# clock.net
KiCad netlist of a schematic drawn in EAGLE
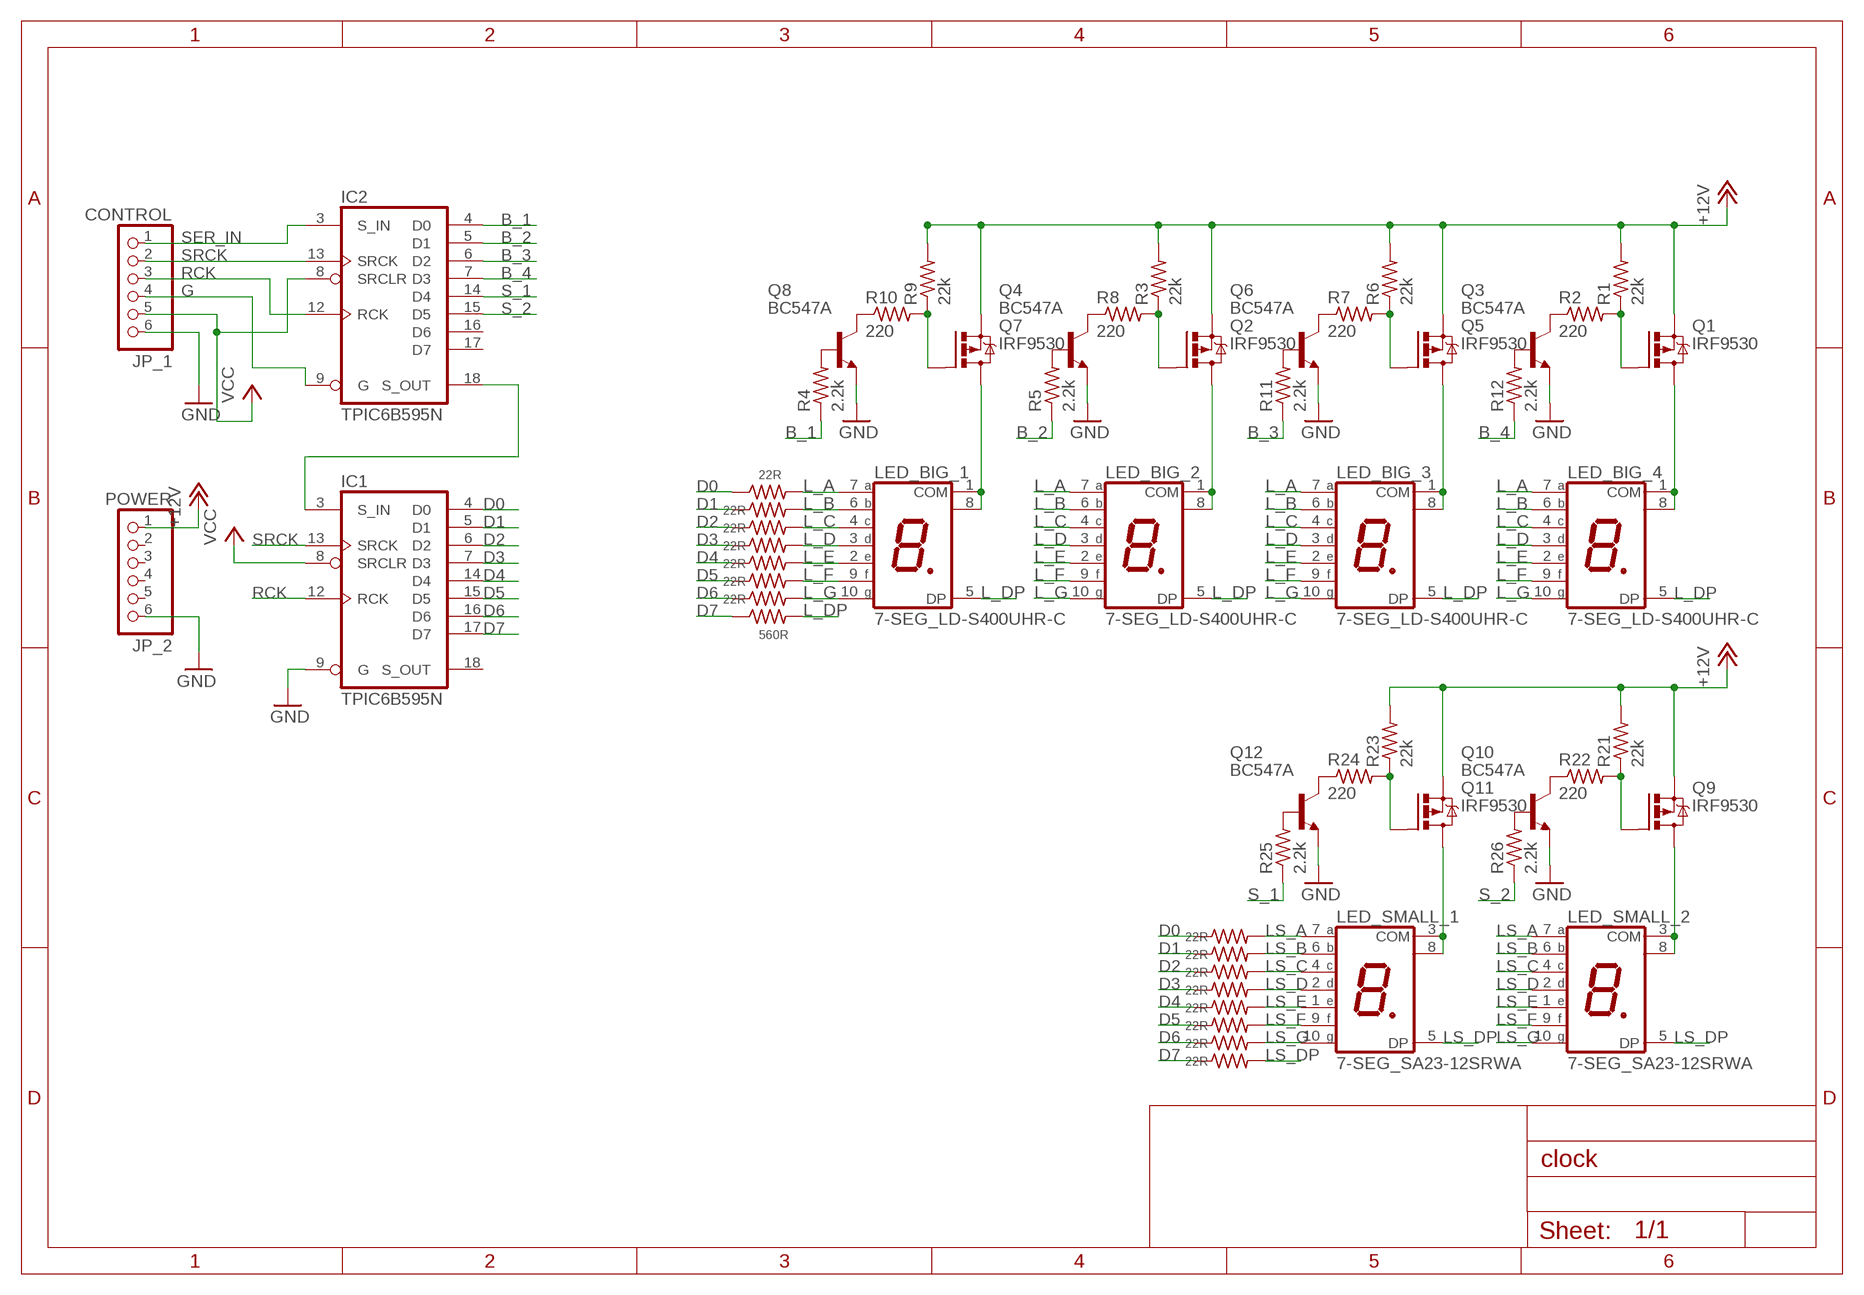
[diagram p0: schematic, sheet 1]

(export (version "E")
  (design (tool "Eeschema 10.0.6"))
  (components
    (comp (ref "CONTROL")
      (value "JP_1")
      (footprint "eagle-import:1X06")
      (libsource (lib "eagle-import") (part "PINHD-1X6"))
    )
    (comp (ref "IC1")
      (value "TPIC6B595N")
      (footprint "eagle-import:DIL20")
      (libsource (lib "eagle-import") (part "TPIC6B595N"))
    )
    (comp (ref "IC2")
      (value "TPIC6B595N")
      (footprint "eagle-import:DIL20")
      (libsource (lib "eagle-import") (part "TPIC6B595N"))
    )
    (comp (ref "LED_BIG_1")
      (value "7-SEG_LD-S400UHR-C")
      (footprint "eagle-import:LD-S400UHR-C")
      (libsource (lib "eagle-import") (part "7-SEG_LD-S400UHR-C"))
    )
    (comp (ref "LED_BIG_2")
      (value "7-SEG_LD-S400UHR-C")
      (footprint "eagle-import:LD-S400UHR-C")
      (libsource (lib "eagle-import") (part "7-SEG_LD-S400UHR-C"))
    )
    (comp (ref "LED_BIG_3")
      (value "7-SEG_LD-S400UHR-C")
      (footprint "eagle-import:LD-S400UHR-C")
      (libsource (lib "eagle-import") (part "7-SEG_LD-S400UHR-C"))
    )
    (comp (ref "LED_BIG_4")
      (value "7-SEG_LD-S400UHR-C")
      (footprint "eagle-import:LD-S400UHR-C")
      (libsource (lib "eagle-import") (part "7-SEG_LD-S400UHR-C"))
    )
    (comp (ref "LED_SMALL_1")
      (value "7-SEG_SA23-12SRWA")
      (footprint "eagle-import:SA23-12SRWA")
      (libsource (lib "eagle-import") (part "7-SEG_SA23-12SRWA"))
    )
    (comp (ref "LED_SMALL_2")
      (value "7-SEG_SA23-12SRWA")
      (footprint "eagle-import:SA23-12SRWA")
      (libsource (lib "eagle-import") (part "7-SEG_SA23-12SRWA"))
    )
    (comp (ref "POWER")
      (value "JP_2")
      (footprint "eagle-import:1X06")
      (libsource (lib "eagle-import") (part "PINHD-1X6"))
    )
    (comp (ref "Q1")
      (value "IRF9530")
      (footprint "eagle-import:TO220BV")
      (libsource (lib "eagle-import") (part "IRF9530"))
    )
    (comp (ref "Q2")
      (value "IRF9530")
      (footprint "eagle-import:TO220BV")
      (libsource (lib "eagle-import") (part "IRF9530"))
    )
    (comp (ref "Q3")
      (value "BC547A")
      (footprint "eagle-import:TO92")
      (libsource (lib "eagle-import") (part "BC547A"))
    )
    (comp (ref "Q4")
      (value "BC547A")
      (footprint "eagle-import:TO92")
      (libsource (lib "eagle-import") (part "BC547A"))
    )
    (comp (ref "Q5")
      (value "IRF9530")
      (footprint "eagle-import:TO220BV")
      (libsource (lib "eagle-import") (part "IRF9530"))
    )
    (comp (ref "Q6")
      (value "BC547A")
      (footprint "eagle-import:TO92")
      (libsource (lib "eagle-import") (part "BC547A"))
    )
    (comp (ref "Q7")
      (value "IRF9530")
      (footprint "eagle-import:TO220BV")
      (libsource (lib "eagle-import") (part "IRF9530"))
    )
    (comp (ref "Q8")
      (value "BC547A")
      (footprint "eagle-import:TO92")
      (libsource (lib "eagle-import") (part "BC547A"))
    )
    (comp (ref "Q9")
      (value "IRF9530")
      (footprint "eagle-import:TO220BV")
      (libsource (lib "eagle-import") (part "IRF9530"))
    )
    (comp (ref "Q10")
      (value "BC547A")
      (footprint "eagle-import:TO92")
      (libsource (lib "eagle-import") (part "BC547A"))
    )
    (comp (ref "Q11")
      (value "IRF9530")
      (footprint "eagle-import:TO220BV")
      (libsource (lib "eagle-import") (part "IRF9530"))
    )
    (comp (ref "Q12")
      (value "BC547A")
      (footprint "eagle-import:TO92")
      (libsource (lib "eagle-import") (part "BC547A"))
    )
    (comp (ref "R1")
      (value "22k")
      (footprint "eagle-import:0207_12")
      (libsource (lib "eagle-import") (part "R-US_0207/12"))
    )
    (comp (ref "R2")
      (value "220")
      (footprint "eagle-import:0207_12")
      (libsource (lib "eagle-import") (part "R-US_0207/12"))
    )
    (comp (ref "R3")
      (value "22k")
      (footprint "eagle-import:0207_12")
      (libsource (lib "eagle-import") (part "R-US_0207/12"))
    )
    (comp (ref "R4")
      (value "2.2k")
      (footprint "eagle-import:0207_12")
      (libsource (lib "eagle-import") (part "R-US_0207/12"))
    )
    (comp (ref "R5")
      (value "2.2k")
      (footprint "eagle-import:0207_12")
      (libsource (lib "eagle-import") (part "R-US_0207/12"))
    )
    (comp (ref "R6")
      (value "22k")
      (footprint "eagle-import:0207_12")
      (libsource (lib "eagle-import") (part "R-US_0207/12"))
    )
    (comp (ref "R7")
      (value "220")
      (footprint "eagle-import:0207_12")
      (libsource (lib "eagle-import") (part "R-US_0207/12"))
    )
    (comp (ref "R8")
      (value "220")
      (footprint "eagle-import:0207_12")
      (libsource (lib "eagle-import") (part "R-US_0207/12"))
    )
    (comp (ref "R9")
      (value "22k")
      (footprint "eagle-import:0207_12")
      (libsource (lib "eagle-import") (part "R-US_0207/12"))
    )
    (comp (ref "R10")
      (value "220")
      (footprint "eagle-import:0207_12")
      (libsource (lib "eagle-import") (part "R-US_0207/12"))
    )
    (comp (ref "R11")
      (value "2.2k")
      (footprint "eagle-import:0207_12")
      (libsource (lib "eagle-import") (part "R-US_0207/12"))
    )
    (comp (ref "R12")
      (value "2.2k")
      (footprint "eagle-import:0207_12")
      (libsource (lib "eagle-import") (part "R-US_0207/12"))
    )
    (comp (ref "R13")
      (value "22R")
      (footprint "eagle-import:0207_12")
      (libsource (lib "eagle-import") (part "R-US_0207/12"))
    )
    (comp (ref "R14")
      (value "22R")
      (footprint "eagle-import:0207_12")
      (libsource (lib "eagle-import") (part "R-US_0207/12"))
    )
    (comp (ref "R15")
      (value "22R")
      (footprint "eagle-import:0207_12")
      (libsource (lib "eagle-import") (part "R-US_0207/12"))
    )
    (comp (ref "R16")
      (value "22R")
      (footprint "eagle-import:0207_12")
      (libsource (lib "eagle-import") (part "R-US_0207/12"))
    )
    (comp (ref "R17")
      (value "22R")
      (footprint "eagle-import:0207_12")
      (libsource (lib "eagle-import") (part "R-US_0207/12"))
    )
    (comp (ref "R18")
      (value "22R")
      (footprint "eagle-import:0207_12")
      (libsource (lib "eagle-import") (part "R-US_0207/12"))
    )
    (comp (ref "R19")
      (value "22R")
      (footprint "eagle-import:0207_12")
      (libsource (lib "eagle-import") (part "R-US_0207/12"))
    )
    (comp (ref "R20")
      (value "560R")
      (footprint "eagle-import:0207_12")
      (libsource (lib "eagle-import") (part "R-US_0207/12"))
    )
    (comp (ref "R21")
      (value "22k")
      (footprint "eagle-import:0207_12")
      (libsource (lib "eagle-import") (part "R-US_0207/12"))
    )
    (comp (ref "R22")
      (value "220")
      (footprint "eagle-import:0207_12")
      (libsource (lib "eagle-import") (part "R-US_0207/12"))
    )
    (comp (ref "R23")
      (value "22k")
      (footprint "eagle-import:0207_12")
      (libsource (lib "eagle-import") (part "R-US_0207/12"))
    )
    (comp (ref "R24")
      (value "220")
      (footprint "eagle-import:0207_12")
      (libsource (lib "eagle-import") (part "R-US_0207/12"))
    )
    (comp (ref "R25")
      (value "2.2k")
      (footprint "eagle-import:0207_12")
      (libsource (lib "eagle-import") (part "R-US_0207/12"))
    )
    (comp (ref "R26")
      (value "2.2k")
      (footprint "eagle-import:0207_12")
      (libsource (lib "eagle-import") (part "R-US_0207/12"))
    )
    (comp (ref "R27")
      (value "22R")
      (footprint "eagle-import:0207_12")
      (libsource (lib "eagle-import") (part "R-US_0207/12"))
    )
    (comp (ref "R28")
      (value "22R")
      (footprint "eagle-import:0207_12")
      (libsource (lib "eagle-import") (part "R-US_0207/12"))
    )
    (comp (ref "R29")
      (value "22R")
      (footprint "eagle-import:0207_12")
      (libsource (lib "eagle-import") (part "R-US_0207/12"))
    )
    (comp (ref "R30")
      (value "22R")
      (footprint "eagle-import:0207_12")
      (libsource (lib "eagle-import") (part "R-US_0207/12"))
    )
    (comp (ref "R31")
      (value "22R")
      (footprint "eagle-import:0207_12")
      (libsource (lib "eagle-import") (part "R-US_0207/12"))
    )
    (comp (ref "R32")
      (value "22R")
      (footprint "eagle-import:0207_12")
      (libsource (lib "eagle-import") (part "R-US_0207/12"))
    )
    (comp (ref "R33")
      (value "22R")
      (footprint "eagle-import:0207_12")
      (libsource (lib "eagle-import") (part "R-US_0207/12"))
    )
    (comp (ref "R34")
      (value "22R")
      (footprint "eagle-import:0207_12")
      (libsource (lib "eagle-import") (part "R-US_0207/12"))
    )
  )
  (nets
    (net (code "1") (name "+12V") (class "Default")
      (node (ref "POWER") (pin "1") (pinfunction "1_1") (pintype "passive"))
      (node (ref "Q1") (pin "S") (pinfunction "S_S") (pintype "passive"))
      (node (ref "Q11") (pin "S") (pinfunction "S_S") (pintype "passive"))
      (node (ref "Q2") (pin "S") (pinfunction "S_S") (pintype "passive"))
      (node (ref "Q5") (pin "S") (pinfunction "S_S") (pintype "passive"))
      (node (ref "Q7") (pin "S") (pinfunction "S_S") (pintype "passive"))
      (node (ref "Q9") (pin "S") (pinfunction "S_S") (pintype "passive"))
      (node (ref "R1") (pin "2") (pinfunction "2_2") (pintype "passive"))
      (node (ref "R21") (pin "2") (pinfunction "2_2") (pintype "passive"))
      (node (ref "R23") (pin "2") (pinfunction "2_2") (pintype "passive"))
      (node (ref "R3") (pin "2") (pinfunction "2_2") (pintype "passive"))
      (node (ref "R6") (pin "2") (pinfunction "2_2") (pintype "passive"))
      (node (ref "R9") (pin "2") (pinfunction "2_2") (pintype "passive"))
    )
    (net (code "2") (name "/B_1") (class "Default")
      (node (ref "IC2") (pin "4") (pinfunction "D0_4") (pintype "tri_state"))
      (node (ref "R4") (pin "1") (pinfunction "1_1") (pintype "passive"))
    )
    (net (code "3") (name "/B_2") (class "Default")
      (node (ref "IC2") (pin "5") (pinfunction "D1_5") (pintype "tri_state"))
      (node (ref "R5") (pin "1") (pinfunction "1_1") (pintype "passive"))
    )
    (net (code "4") (name "/B_3") (class "Default")
      (node (ref "IC2") (pin "6") (pinfunction "D2_6") (pintype "tri_state"))
      (node (ref "R11") (pin "1") (pinfunction "1_1") (pintype "passive"))
    )
    (net (code "5") (name "/B_4") (class "Default")
      (node (ref "IC2") (pin "7") (pinfunction "D3_7") (pintype "tri_state"))
      (node (ref "R12") (pin "1") (pinfunction "1_1") (pintype "passive"))
    )
    (net (code "6") (name "/D0") (class "Default")
      (node (ref "IC1") (pin "4") (pinfunction "D0_4") (pintype "tri_state"))
      (node (ref "R13") (pin "1") (pinfunction "1_1") (pintype "passive"))
      (node (ref "R27") (pin "1") (pinfunction "1_1") (pintype "passive"))
    )
    (net (code "7") (name "/D1") (class "Default")
      (node (ref "IC1") (pin "5") (pinfunction "D1_5") (pintype "tri_state"))
      (node (ref "R14") (pin "1") (pinfunction "1_1") (pintype "passive"))
      (node (ref "R28") (pin "1") (pinfunction "1_1") (pintype "passive"))
    )
    (net (code "8") (name "/D2") (class "Default")
      (node (ref "IC1") (pin "6") (pinfunction "D2_6") (pintype "tri_state"))
      (node (ref "R15") (pin "1") (pinfunction "1_1") (pintype "passive"))
      (node (ref "R29") (pin "1") (pinfunction "1_1") (pintype "passive"))
    )
    (net (code "9") (name "/D3") (class "Default")
      (node (ref "IC1") (pin "7") (pinfunction "D3_7") (pintype "tri_state"))
      (node (ref "R16") (pin "1") (pinfunction "1_1") (pintype "passive"))
      (node (ref "R30") (pin "1") (pinfunction "1_1") (pintype "passive"))
    )
    (net (code "10") (name "/D4") (class "Default")
      (node (ref "IC1") (pin "14") (pinfunction "D4_14") (pintype "tri_state"))
      (node (ref "R17") (pin "1") (pinfunction "1_1") (pintype "passive"))
      (node (ref "R31") (pin "1") (pinfunction "1_1") (pintype "passive"))
    )
    (net (code "11") (name "/D5") (class "Default")
      (node (ref "IC1") (pin "15") (pinfunction "D5_15") (pintype "tri_state"))
      (node (ref "R18") (pin "1") (pinfunction "1_1") (pintype "passive"))
      (node (ref "R32") (pin "1") (pinfunction "1_1") (pintype "passive"))
    )
    (net (code "12") (name "/D6") (class "Default")
      (node (ref "IC1") (pin "16") (pinfunction "D6_16") (pintype "tri_state"))
      (node (ref "R19") (pin "1") (pinfunction "1_1") (pintype "passive"))
      (node (ref "R33") (pin "1") (pinfunction "1_1") (pintype "passive"))
    )
    (net (code "13") (name "/D7") (class "Default")
      (node (ref "IC1") (pin "17") (pinfunction "D7_17") (pintype "tri_state"))
      (node (ref "R20") (pin "1") (pinfunction "1_1") (pintype "passive"))
      (node (ref "R34") (pin "1") (pinfunction "1_1") (pintype "passive"))
    )
    (net (code "14") (name "/G") (class "Default")
      (node (ref "CONTROL") (pin "4") (pinfunction "4_4") (pintype "passive"))
      (node (ref "IC2") (pin "9") (pinfunction "G_9") (pintype "input"))
    )
    (net (code "15") (name "/LS_A") (class "Default")
      (node (ref "LED_SMALL_1") (pin "7") (pinfunction "A_7") (pintype "passive"))
      (node (ref "LED_SMALL_2") (pin "7") (pinfunction "A_7") (pintype "passive"))
      (node (ref "R27") (pin "2") (pinfunction "2_2") (pintype "passive"))
    )
    (net (code "16") (name "/LS_B") (class "Default")
      (node (ref "LED_SMALL_1") (pin "6") (pinfunction "B_6") (pintype "passive"))
      (node (ref "LED_SMALL_2") (pin "6") (pinfunction "B_6") (pintype "passive"))
      (node (ref "R28") (pin "2") (pinfunction "2_2") (pintype "passive"))
    )
    (net (code "17") (name "/LS_C") (class "Default")
      (node (ref "LED_SMALL_1") (pin "4") (pinfunction "C_4") (pintype "passive"))
      (node (ref "LED_SMALL_2") (pin "4") (pinfunction "C_4") (pintype "passive"))
      (node (ref "R29") (pin "2") (pinfunction "2_2") (pintype "passive"))
    )
    (net (code "18") (name "/LS_D") (class "Default")
      (node (ref "LED_SMALL_1") (pin "2") (pinfunction "D_2") (pintype "passive"))
      (node (ref "LED_SMALL_2") (pin "2") (pinfunction "D_2") (pintype "passive"))
      (node (ref "R30") (pin "2") (pinfunction "2_2") (pintype "passive"))
    )
    (net (code "19") (name "/LS_DP") (class "Default")
      (node (ref "LED_SMALL_1") (pin "5") (pinfunction "DP_5") (pintype "passive"))
      (node (ref "LED_SMALL_2") (pin "5") (pinfunction "DP_5") (pintype "passive"))
      (node (ref "R34") (pin "2") (pinfunction "2_2") (pintype "passive"))
    )
    (net (code "20") (name "/LS_E") (class "Default")
      (node (ref "LED_SMALL_1") (pin "1") (pinfunction "E_1") (pintype "passive"))
      (node (ref "LED_SMALL_2") (pin "1") (pinfunction "E_1") (pintype "passive"))
      (node (ref "R31") (pin "2") (pinfunction "2_2") (pintype "passive"))
    )
    (net (code "21") (name "/LS_F") (class "Default")
      (node (ref "LED_SMALL_1") (pin "9") (pinfunction "F_9") (pintype "passive"))
      (node (ref "LED_SMALL_2") (pin "9") (pinfunction "F_9") (pintype "passive"))
      (node (ref "R32") (pin "2") (pinfunction "2_2") (pintype "passive"))
    )
    (net (code "22") (name "/LS_G") (class "Default")
      (node (ref "LED_SMALL_1") (pin "10") (pinfunction "G_10") (pintype "passive"))
      (node (ref "LED_SMALL_2") (pin "10") (pinfunction "G_10") (pintype "passive"))
      (node (ref "R33") (pin "2") (pinfunction "2_2") (pintype "passive"))
    )
    (net (code "23") (name "/L_A") (class "Default")
      (node (ref "LED_BIG_1") (pin "7") (pinfunction "A_7") (pintype "passive"))
      (node (ref "LED_BIG_2") (pin "7") (pinfunction "A_7") (pintype "passive"))
      (node (ref "LED_BIG_3") (pin "7") (pinfunction "A_7") (pintype "passive"))
      (node (ref "LED_BIG_4") (pin "7") (pinfunction "A_7") (pintype "passive"))
      (node (ref "R13") (pin "2") (pinfunction "2_2") (pintype "passive"))
    )
    (net (code "24") (name "/L_B") (class "Default")
      (node (ref "LED_BIG_1") (pin "6") (pinfunction "B_6") (pintype "passive"))
      (node (ref "LED_BIG_2") (pin "6") (pinfunction "B_6") (pintype "passive"))
      (node (ref "LED_BIG_3") (pin "6") (pinfunction "B_6") (pintype "passive"))
      (node (ref "LED_BIG_4") (pin "6") (pinfunction "B_6") (pintype "passive"))
      (node (ref "R14") (pin "2") (pinfunction "2_2") (pintype "passive"))
    )
    (net (code "25") (name "/L_C") (class "Default")
      (node (ref "LED_BIG_1") (pin "4") (pinfunction "C_4") (pintype "passive"))
      (node (ref "LED_BIG_2") (pin "4") (pinfunction "C_4") (pintype "passive"))
      (node (ref "LED_BIG_3") (pin "4") (pinfunction "C_4") (pintype "passive"))
      (node (ref "LED_BIG_4") (pin "4") (pinfunction "C_4") (pintype "passive"))
      (node (ref "R15") (pin "2") (pinfunction "2_2") (pintype "passive"))
    )
    (net (code "26") (name "/L_D") (class "Default")
      (node (ref "LED_BIG_1") (pin "3") (pinfunction "D_3") (pintype "passive"))
      (node (ref "LED_BIG_2") (pin "3") (pinfunction "D_3") (pintype "passive"))
      (node (ref "LED_BIG_3") (pin "3") (pinfunction "D_3") (pintype "passive"))
      (node (ref "LED_BIG_4") (pin "3") (pinfunction "D_3") (pintype "passive"))
      (node (ref "R16") (pin "2") (pinfunction "2_2") (pintype "passive"))
    )
    (net (code "27") (name "/L_DP") (class "Default")
      (node (ref "LED_BIG_1") (pin "5") (pinfunction "DP_5") (pintype "passive"))
      (node (ref "LED_BIG_2") (pin "5") (pinfunction "DP_5") (pintype "passive"))
      (node (ref "LED_BIG_3") (pin "5") (pinfunction "DP_5") (pintype "passive"))
      (node (ref "LED_BIG_4") (pin "5") (pinfunction "DP_5") (pintype "passive"))
      (node (ref "R20") (pin "2") (pinfunction "2_2") (pintype "passive"))
    )
    (net (code "28") (name "/L_E") (class "Default")
      (node (ref "LED_BIG_1") (pin "2") (pinfunction "E_2") (pintype "passive"))
      (node (ref "LED_BIG_2") (pin "2") (pinfunction "E_2") (pintype "passive"))
      (node (ref "LED_BIG_3") (pin "2") (pinfunction "E_2") (pintype "passive"))
      (node (ref "LED_BIG_4") (pin "2") (pinfunction "E_2") (pintype "passive"))
      (node (ref "R17") (pin "2") (pinfunction "2_2") (pintype "passive"))
    )
    (net (code "29") (name "/L_F") (class "Default")
      (node (ref "LED_BIG_1") (pin "9") (pinfunction "F_9") (pintype "passive"))
      (node (ref "LED_BIG_2") (pin "9") (pinfunction "F_9") (pintype "passive"))
      (node (ref "LED_BIG_3") (pin "9") (pinfunction "F_9") (pintype "passive"))
      (node (ref "LED_BIG_4") (pin "9") (pinfunction "F_9") (pintype "passive"))
      (node (ref "R18") (pin "2") (pinfunction "2_2") (pintype "passive"))
    )
    (net (code "30") (name "/L_G") (class "Default")
      (node (ref "LED_BIG_1") (pin "10") (pinfunction "G_10") (pintype "passive"))
      (node (ref "LED_BIG_2") (pin "10") (pinfunction "G_10") (pintype "passive"))
      (node (ref "LED_BIG_3") (pin "10") (pinfunction "G_10") (pintype "passive"))
      (node (ref "LED_BIG_4") (pin "10") (pinfunction "G_10") (pintype "passive"))
      (node (ref "R19") (pin "2") (pinfunction "2_2") (pintype "passive"))
    )
    (net (code "31") (name "/RCK") (class "Default")
      (node (ref "CONTROL") (pin "3") (pinfunction "3_3") (pintype "passive"))
      (node (ref "IC1") (pin "12") (pinfunction "RCK_12") (pintype "input"))
      (node (ref "IC2") (pin "12") (pinfunction "RCK_12") (pintype "input"))
    )
    (net (code "32") (name "/SER_IN") (class "Default")
      (node (ref "CONTROL") (pin "1") (pinfunction "1_1") (pintype "passive"))
      (node (ref "IC2") (pin "3") (pinfunction "S_IN_3") (pintype "input"))
    )
    (net (code "33") (name "/SRCK") (class "Default")
      (node (ref "CONTROL") (pin "2") (pinfunction "2_2") (pintype "passive"))
      (node (ref "IC1") (pin "13") (pinfunction "SRCK_13") (pintype "input"))
      (node (ref "IC2") (pin "13") (pinfunction "SRCK_13") (pintype "input"))
    )
    (net (code "34") (name "/S_1") (class "Default")
      (node (ref "IC2") (pin "14") (pinfunction "D4_14") (pintype "tri_state"))
      (node (ref "R25") (pin "1") (pinfunction "1_1") (pintype "passive"))
    )
    (net (code "35") (name "/S_2") (class "Default")
      (node (ref "IC2") (pin "15") (pinfunction "D5_15") (pintype "tri_state"))
      (node (ref "R26") (pin "1") (pinfunction "1_1") (pintype "passive"))
    )
    (net (code "36") (name "GND") (class "Default")
      (node (ref "CONTROL") (pin "6") (pinfunction "6_6") (pintype "passive"))
      (node (ref "IC1") (pin "9") (pinfunction "G_9") (pintype "input"))
      (node (ref "POWER") (pin "6") (pinfunction "6_6") (pintype "passive"))
      (node (ref "Q10") (pin "1") (pinfunction "E_1") (pintype "passive"))
      (node (ref "Q12") (pin "1") (pinfunction "E_1") (pintype "passive"))
      (node (ref "Q3") (pin "1") (pinfunction "E_1") (pintype "passive"))
      (node (ref "Q4") (pin "1") (pinfunction "E_1") (pintype "passive"))
      (node (ref "Q6") (pin "1") (pinfunction "E_1") (pintype "passive"))
      (node (ref "Q8") (pin "1") (pinfunction "E_1") (pintype "passive"))
    )
    (net (code "37") (name "Net-(IC1A-S_IN)") (class "Default")
      (node (ref "IC1") (pin "3") (pinfunction "S_IN_3") (pintype "input"))
      (node (ref "IC2") (pin "18") (pinfunction "S_OUT_18") (pintype "tri_state"))
    )
    (net (code "38") (name "Net-(LED_BIG_1-COM-Pad1)") (class "Default")
      (node (ref "LED_BIG_1") (pin "1") (pinfunction "COM_1") (pintype "passive"))
      (node (ref "LED_BIG_1") (pin "8") (pinfunction "COM_8") (pintype "passive"))
      (node (ref "Q7") (pin "D") (pinfunction "D_D") (pintype "passive"))
    )
    (net (code "39") (name "Net-(LED_BIG_2-COM-Pad1)") (class "Default")
      (node (ref "LED_BIG_2") (pin "1") (pinfunction "COM_1") (pintype "passive"))
      (node (ref "LED_BIG_2") (pin "8") (pinfunction "COM_8") (pintype "passive"))
      (node (ref "Q2") (pin "D") (pinfunction "D_D") (pintype "passive"))
    )
    (net (code "40") (name "Net-(LED_BIG_3-COM-Pad1)") (class "Default")
      (node (ref "LED_BIG_3") (pin "1") (pinfunction "COM_1") (pintype "passive"))
      (node (ref "LED_BIG_3") (pin "8") (pinfunction "COM_8") (pintype "passive"))
      (node (ref "Q5") (pin "D") (pinfunction "D_D") (pintype "passive"))
    )
    (net (code "41") (name "Net-(LED_BIG_4-COM-Pad1)") (class "Default")
      (node (ref "LED_BIG_4") (pin "1") (pinfunction "COM_1") (pintype "passive"))
      (node (ref "LED_BIG_4") (pin "8") (pinfunction "COM_8") (pintype "passive"))
      (node (ref "Q1") (pin "D") (pinfunction "D_D") (pintype "passive"))
    )
    (net (code "42") (name "Net-(LED_SMALL_1-COM-Pad3)") (class "Default")
      (node (ref "LED_SMALL_1") (pin "3") (pinfunction "COM_3") (pintype "passive"))
      (node (ref "LED_SMALL_1") (pin "8") (pinfunction "COM_8") (pintype "passive"))
      (node (ref "Q11") (pin "D") (pinfunction "D_D") (pintype "passive"))
    )
    (net (code "43") (name "Net-(LED_SMALL_2-COM-Pad3)") (class "Default")
      (node (ref "LED_SMALL_2") (pin "3") (pinfunction "COM_3") (pintype "passive"))
      (node (ref "LED_SMALL_2") (pin "8") (pinfunction "COM_8") (pintype "passive"))
      (node (ref "Q9") (pin "D") (pinfunction "D_D") (pintype "passive"))
    )
    (net (code "44") (name "Net-(Q1-PadG)") (class "Default")
      (node (ref "Q1") (pin "G") (pinfunction "G_G") (pintype "passive"))
      (node (ref "R1") (pin "1") (pinfunction "1_1") (pintype "passive"))
      (node (ref "R2") (pin "2") (pinfunction "2_2") (pintype "passive"))
    )
    (net (code "45") (name "Net-(Q2-PadG)") (class "Default")
      (node (ref "Q2") (pin "G") (pinfunction "G_G") (pintype "passive"))
      (node (ref "R3") (pin "1") (pinfunction "1_1") (pintype "passive"))
      (node (ref "R8") (pin "2") (pinfunction "2_2") (pintype "passive"))
    )
    (net (code "46") (name "Net-(Q3-B)") (class "Default")
      (node (ref "Q3") (pin "2") (pinfunction "B_2") (pintype "passive"))
      (node (ref "R12") (pin "2") (pinfunction "2_2") (pintype "passive"))
    )
    (net (code "47") (name "Net-(Q3-C)") (class "Default")
      (node (ref "Q3") (pin "3") (pinfunction "C_3") (pintype "passive"))
      (node (ref "R2") (pin "1") (pinfunction "1_1") (pintype "passive"))
    )
    (net (code "48") (name "Net-(Q4-B)") (class "Default")
      (node (ref "Q4") (pin "2") (pinfunction "B_2") (pintype "passive"))
      (node (ref "R5") (pin "2") (pinfunction "2_2") (pintype "passive"))
    )
    (net (code "49") (name "Net-(Q4-C)") (class "Default")
      (node (ref "Q4") (pin "3") (pinfunction "C_3") (pintype "passive"))
      (node (ref "R8") (pin "1") (pinfunction "1_1") (pintype "passive"))
    )
    (net (code "50") (name "Net-(Q5-PadG)") (class "Default")
      (node (ref "Q5") (pin "G") (pinfunction "G_G") (pintype "passive"))
      (node (ref "R6") (pin "1") (pinfunction "1_1") (pintype "passive"))
      (node (ref "R7") (pin "2") (pinfunction "2_2") (pintype "passive"))
    )
    (net (code "51") (name "Net-(Q6-B)") (class "Default")
      (node (ref "Q6") (pin "2") (pinfunction "B_2") (pintype "passive"))
      (node (ref "R11") (pin "2") (pinfunction "2_2") (pintype "passive"))
    )
    (net (code "52") (name "Net-(Q6-C)") (class "Default")
      (node (ref "Q6") (pin "3") (pinfunction "C_3") (pintype "passive"))
      (node (ref "R7") (pin "1") (pinfunction "1_1") (pintype "passive"))
    )
    (net (code "53") (name "Net-(Q7-PadG)") (class "Default")
      (node (ref "Q7") (pin "G") (pinfunction "G_G") (pintype "passive"))
      (node (ref "R10") (pin "2") (pinfunction "2_2") (pintype "passive"))
      (node (ref "R9") (pin "1") (pinfunction "1_1") (pintype "passive"))
    )
    (net (code "54") (name "Net-(Q8-B)") (class "Default")
      (node (ref "Q8") (pin "2") (pinfunction "B_2") (pintype "passive"))
      (node (ref "R4") (pin "2") (pinfunction "2_2") (pintype "passive"))
    )
    (net (code "55") (name "Net-(Q8-C)") (class "Default")
      (node (ref "Q8") (pin "3") (pinfunction "C_3") (pintype "passive"))
      (node (ref "R10") (pin "1") (pinfunction "1_1") (pintype "passive"))
    )
    (net (code "56") (name "Net-(Q9-PadG)") (class "Default")
      (node (ref "Q9") (pin "G") (pinfunction "G_G") (pintype "passive"))
      (node (ref "R21") (pin "1") (pinfunction "1_1") (pintype "passive"))
      (node (ref "R22") (pin "2") (pinfunction "2_2") (pintype "passive"))
    )
    (net (code "57") (name "Net-(Q10-B)") (class "Default")
      (node (ref "Q10") (pin "2") (pinfunction "B_2") (pintype "passive"))
      (node (ref "R26") (pin "2") (pinfunction "2_2") (pintype "passive"))
    )
    (net (code "58") (name "Net-(Q10-C)") (class "Default")
      (node (ref "Q10") (pin "3") (pinfunction "C_3") (pintype "passive"))
      (node (ref "R22") (pin "1") (pinfunction "1_1") (pintype "passive"))
    )
    (net (code "59") (name "Net-(Q11-PadG)") (class "Default")
      (node (ref "Q11") (pin "G") (pinfunction "G_G") (pintype "passive"))
      (node (ref "R23") (pin "1") (pinfunction "1_1") (pintype "passive"))
      (node (ref "R24") (pin "2") (pinfunction "2_2") (pintype "passive"))
    )
    (net (code "60") (name "Net-(Q12-B)") (class "Default")
      (node (ref "Q12") (pin "2") (pinfunction "B_2") (pintype "passive"))
      (node (ref "R25") (pin "2") (pinfunction "2_2") (pintype "passive"))
    )
    (net (code "61") (name "Net-(Q12-C)") (class "Default")
      (node (ref "Q12") (pin "3") (pinfunction "C_3") (pintype "passive"))
      (node (ref "R24") (pin "1") (pinfunction "1_1") (pintype "passive"))
    )
    (net (code "62") (name "VCC") (class "Default")
      (node (ref "CONTROL") (pin "5") (pinfunction "5_5") (pintype "passive"))
      (node (ref "IC1") (pin "8") (pinfunction "SRCLR_8") (pintype "input"))
      (node (ref "IC2") (pin "8") (pinfunction "SRCLR_8") (pintype "input"))
    )
    (net (code "63") (name "unconnected-(IC1A-S_OUT-Pad18)") (class "Default")
      (node (ref "IC1") (pin "18") (pinfunction "S_OUT_18") (pintype "tri_state"))
    )
    (net (code "64") (name "unconnected-(IC2A-D6-Pad16)") (class "Default")
      (node (ref "IC2") (pin "16") (pinfunction "D6_16") (pintype "tri_state"))
    )
    (net (code "65") (name "unconnected-(IC2A-D7-Pad17)") (class "Default")
      (node (ref "IC2") (pin "17") (pinfunction "D7_17") (pintype "tri_state"))
    )
    (net (code "66") (name "unconnected-(POWER-Pad2)") (class "Default")
      (node (ref "POWER") (pin "2") (pinfunction "2_2") (pintype "passive"))
    )
    (net (code "67") (name "unconnected-(POWER-Pad3)") (class "Default")
      (node (ref "POWER") (pin "3") (pinfunction "3_3") (pintype "passive"))
    )
    (net (code "68") (name "unconnected-(POWER-Pad4)") (class "Default")
      (node (ref "POWER") (pin "4") (pinfunction "4_4") (pintype "passive"))
    )
    (net (code "69") (name "unconnected-(POWER-Pad5)") (class "Default")
      (node (ref "POWER") (pin "5") (pinfunction "5_5") (pintype "passive"))
    )
  )
)
